# IR_robottino_tracking_schematics.net
KiCad netlist of a schematic drawn in Altium Designer
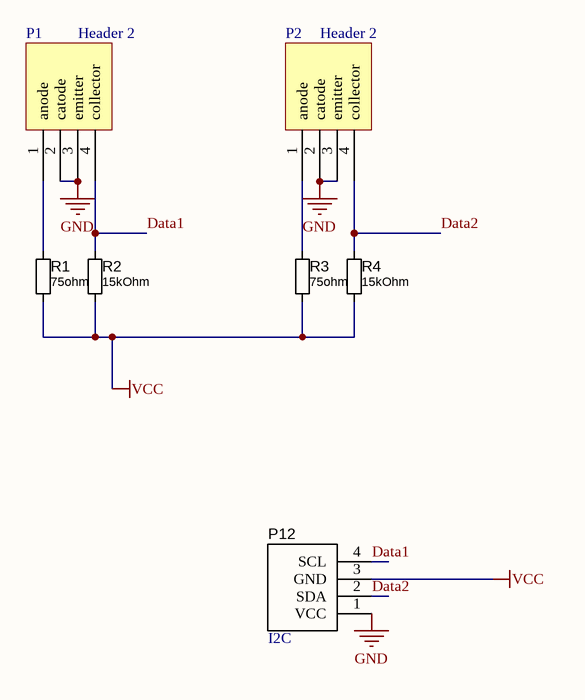
[diagram p0: IR_robottino_tracking_schematics.SchDoc]

(export (version "E")
  (design (tool "Eeschema 10.0.6"))
  (components
    (comp (ref "P1")
      (value "Header 2")
      (footprint "TCRT 1000")
      (description "Header, 2-Pin")
      (fields (field (name "PUBLISHER") "Altium Limited"))
      (libsource (lib "marcolib") (part "TCRT 1000"))
    )
    (comp (ref "P2")
      (value "Header 2")
      (footprint "TCRT 1000")
      (description "Header, 2-Pin")
      (fields (field (name "PUBLISHER") "Altium Limited"))
      (libsource (lib "marcolib") (part "TCRT 1000"))
    )
    (comp (ref "P12")
      (value "I2C")
      (footprint "TYCO/215079-4")
      (description "Micromatch I2C Connector")
      (libsource (lib "andylib") (part "Micromatch-I2C"))
    )
    (comp (ref "R1")
      (value "75ohm")
      (footprint "R/1206")
      (description "Resistor")
      (fields (field (name "PUBLISHER") "Altium Limited"))
      (libsource (lib "") (part "R_1"))
    )
    (comp (ref "R2")
      (value "15kOhm")
      (footprint "R/0805")
      (description "Resistor")
      (fields (field (name "PUBLISHER") "Altium Limited"))
      (libsource (lib "andylib") (part "R"))
    )
    (comp (ref "R3")
      (value "75ohm")
      (footprint "R/1206")
      (description "Resistor")
      (fields (field (name "PUBLISHER") "Altium Limited"))
      (libsource (lib "andylib") (part "R"))
    )
    (comp (ref "R4")
      (value "15kOhm")
      (footprint "R/0805")
      (description "Resistor")
      (fields (field (name "PUBLISHER") "Altium Limited"))
      (libsource (lib "andylib") (part "R"))
    )
  )
  (nets
    (net (code "1") (name "/Data1") (class "Default")
      (node (ref "P1") (pin "4") (pinfunction "collector_4") (pintype "passive"))
      (node (ref "P12") (pin "4") (pinfunction "SCL_4") (pintype "passive"))
      (node (ref "R2") (pin "2") (pinfunction "2_2") (pintype "passive"))
    )
    (net (code "2") (name "/Data2") (class "Default")
      (node (ref "P12") (pin "2") (pinfunction "SDA_2") (pintype "passive"))
      (node (ref "P2") (pin "4") (pinfunction "collector_4") (pintype "passive"))
      (node (ref "R4") (pin "2") (pinfunction "2_2") (pintype "passive"))
    )
    (net (code "3") (name "GND") (class "Default")
      (node (ref "P1") (pin "2") (pinfunction "catode_2") (pintype "passive"))
      (node (ref "P1") (pin "3") (pinfunction "emitter_3") (pintype "passive"))
      (node (ref "P12") (pin "1") (pinfunction "VCC_1") (pintype "passive"))
      (node (ref "P2") (pin "2") (pinfunction "catode_2") (pintype "passive"))
      (node (ref "P2") (pin "3") (pinfunction "emitter_3") (pintype "passive"))
    )
    (net (code "4") (name "Net-(P1-anode)") (class "Default")
      (node (ref "P1") (pin "1") (pinfunction "anode_1") (pintype "passive"))
      (node (ref "R1") (pin "1") (pinfunction "1_1") (pintype "passive"))
    )
    (net (code "5") (name "Net-(P2-anode)") (class "Default")
      (node (ref "P2") (pin "1") (pinfunction "anode_1") (pintype "passive"))
      (node (ref "R3") (pin "2") (pinfunction "2_2") (pintype "passive"))
    )
    (net (code "6") (name "VCC") (class "Default")
      (node (ref "P12") (pin "3") (pinfunction "GND_3") (pintype "passive"))
      (node (ref "R1") (pin "2") (pinfunction "2_2") (pintype "passive"))
      (node (ref "R2") (pin "1") (pinfunction "1_1") (pintype "passive"))
      (node (ref "R3") (pin "1") (pinfunction "1_1") (pintype "passive"))
      (node (ref "R4") (pin "1") (pinfunction "1_1") (pintype "passive"))
    )
  )
)
